# Rs232.net
KiCad netlist of a schematic drawn in Altium Designer
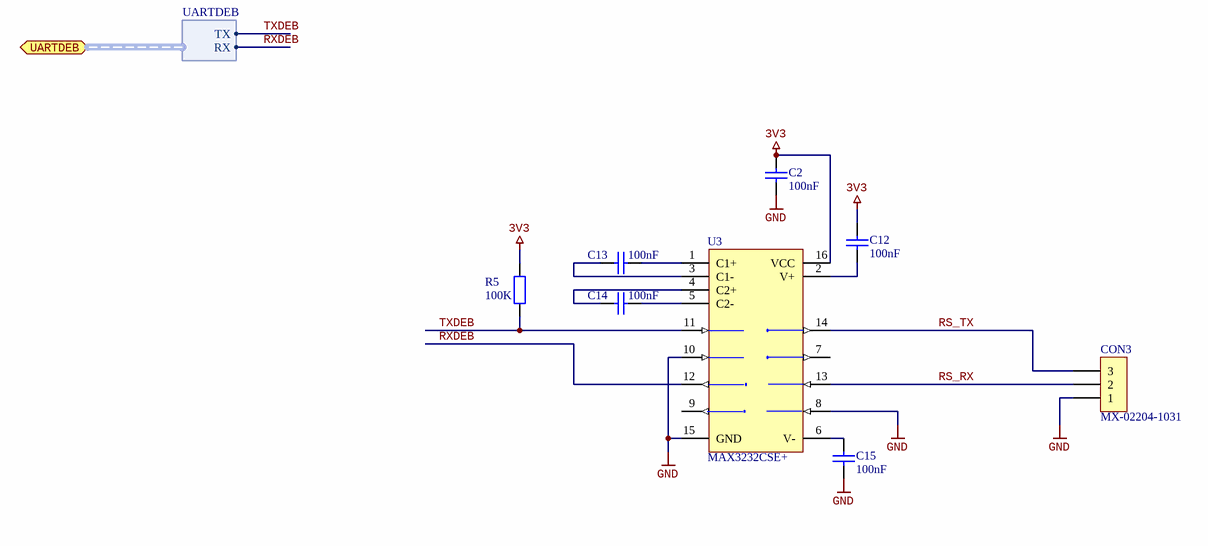
[diagram p0: Rs232.SchDoc]

(export (version "E")
  (design (tool "Eeschema 10.0.6"))
  (components
    (comp (ref "C2")
      (value "100nF")
      (footprint "CAPC1608N")
      (description "Capacitor")
      (libsource (lib "Discrete") (part "Capacitor"))
    )
    (comp (ref "C12")
      (value "100nF")
      (footprint "CAPC1608N")
      (description "Capacitor")
      (libsource (lib "Discrete") (part "Capacitor"))
    )
    (comp (ref "C13")
      (value "100nF")
      (footprint "CAPC1608N")
      (description "Capacitor")
      (libsource (lib "Discrete") (part "Capacitor"))
    )
    (comp (ref "C14")
      (value "100nF")
      (footprint "CAPC1608N")
      (description "Capacitor")
      (libsource (lib "Discrete") (part "Capacitor"))
    )
    (comp (ref "C15")
      (value "100nF")
      (footprint "CAPC1608N")
      (description "Capacitor")
      (libsource (lib "Discrete") (part "Capacitor"))
    )
    (comp (ref "CON3")
      (value "MX-02204-1031")
      (footprint "Connectors:MX-02204-1031")
      (description "Pith 2.54mm, 3-pin")
      (libsource (lib "Connectors") (part "MX-02204-1031"))
    )
    (comp (ref "R5")
      (value "100K")
      (footprint "RESC1608N")
      (description "Resistor")
      (fields (field (name "POWER") "0W") (field (name "TOLERANCE") "5%"))
      (libsource (lib "Discrete") (part "Resistor"))
    )
    (comp (ref "U3")
      (value "MAX3232CSE+")
      (footprint "SO16_N")
      (description "3.0V TO 5.5V, Low-Power, up to 1Mbps, True RS-232 Transceiver Using Four 0.1µF External Capacitor")
      (fields (field (name "PUBLISHER") "Altium Limited"))
      (libsource (lib "Maxim Communication Transceiver") (part "MAX3232CUE"))
    )
  )
  (nets
    (net (code "2") (name "/RS_RX") (class "Default")
      (node (ref "CON3") (pin "2") (pinfunction "2_2") (pintype "passive"))
      (node (ref "U3") (pin "13") (pinfunction "R1IN_13") (pintype "input"))
    )
    (net (code "3") (name "/RS_TX") (class "Default")
      (node (ref "CON3") (pin "3") (pinfunction "3_3") (pintype "passive"))
      (node (ref "U3") (pin "14") (pinfunction "T1OUT_14") (pintype "output"))
    )
    (net (code "4") (name "/RXDEB") (class "Default")
      (node (ref "U3") (pin "12") (pinfunction "R1OUT_12") (pintype "output"))
    )
    (net (code "5") (name "/TXDEB") (class "Default")
      (node (ref "R5") (pin "1") (pinfunction "1_1") (pintype "passive"))
      (node (ref "U3") (pin "11") (pinfunction "T1IN_11") (pintype "input"))
    )
    (net (code "7") (name "3V3") (class "Default")
      (node (ref "C12") (pin "2") (pinfunction "2_2") (pintype "passive"))
      (node (ref "C2") (pin "2") (pinfunction "2_2") (pintype "passive"))
      (node (ref "R5") (pin "2") (pinfunction "2_2") (pintype "passive"))
      (node (ref "U3") (pin "16") (pinfunction "VCC_16") (pintype "power_in"))
    )
    (net (code "8") (name "GND") (class "Default")
      (node (ref "C15") (pin "1") (pinfunction "1_1") (pintype "passive"))
      (node (ref "C2") (pin "1") (pinfunction "1_1") (pintype "passive"))
      (node (ref "CON3") (pin "1") (pinfunction "1_1") (pintype "passive"))
      (node (ref "U3") (pin "10") (pinfunction "T2IN_10") (pintype "input"))
      (node (ref "U3") (pin "15") (pinfunction "GND_15") (pintype "power_in"))
      (node (ref "U3") (pin "8") (pinfunction "R2IN_8") (pintype "input"))
    )
    (net (code "9") (name "Net-(U3-C1+)") (class "Default")
      (node (ref "C13") (pin "2") (pinfunction "2_2") (pintype "passive"))
      (node (ref "U3") (pin "1") (pinfunction "C1+_1") (pintype "passive"))
    )
    (net (code "10") (name "Net-(U3-C1-)") (class "Default")
      (node (ref "C13") (pin "1") (pinfunction "1_1") (pintype "passive"))
      (node (ref "U3") (pin "3") (pinfunction "C1-_3") (pintype "passive"))
    )
    (net (code "11") (name "Net-(U3-C2+)") (class "Default")
      (node (ref "C14") (pin "1") (pinfunction "1_1") (pintype "passive"))
      (node (ref "U3") (pin "4") (pinfunction "C2+_4") (pintype "passive"))
    )
    (net (code "12") (name "Net-(U3-C2-)") (class "Default")
      (node (ref "C14") (pin "2") (pinfunction "2_2") (pintype "passive"))
      (node (ref "U3") (pin "5") (pinfunction "C2-_5") (pintype "passive"))
    )
    (net (code "13") (name "Net-(U3-V+)") (class "Default")
      (node (ref "C12") (pin "1") (pinfunction "1_1") (pintype "passive"))
      (node (ref "U3") (pin "2") (pinfunction "V+_2") (pintype "power_in"))
    )
    (net (code "14") (name "Net-(U3-V-)") (class "Default")
      (node (ref "C15") (pin "2") (pinfunction "2_2") (pintype "passive"))
      (node (ref "U3") (pin "6") (pinfunction "V-_6") (pintype "power_in"))
    )
    (net (code "15") (name "unconnected-(U3-R2OUT-Pad9)") (class "Default")
      (node (ref "U3") (pin "9") (pinfunction "R2OUT_9") (pintype "output"))
    )
    (net (code "16") (name "unconnected-(U3-T2OUT-Pad7)") (class "Default")
      (node (ref "U3") (pin "7") (pinfunction "T2OUT_7") (pintype "output"))
    )
  )
)
